# KeepUntil-v1_0.net
KiCad netlist of a schematic drawn in EAGLE
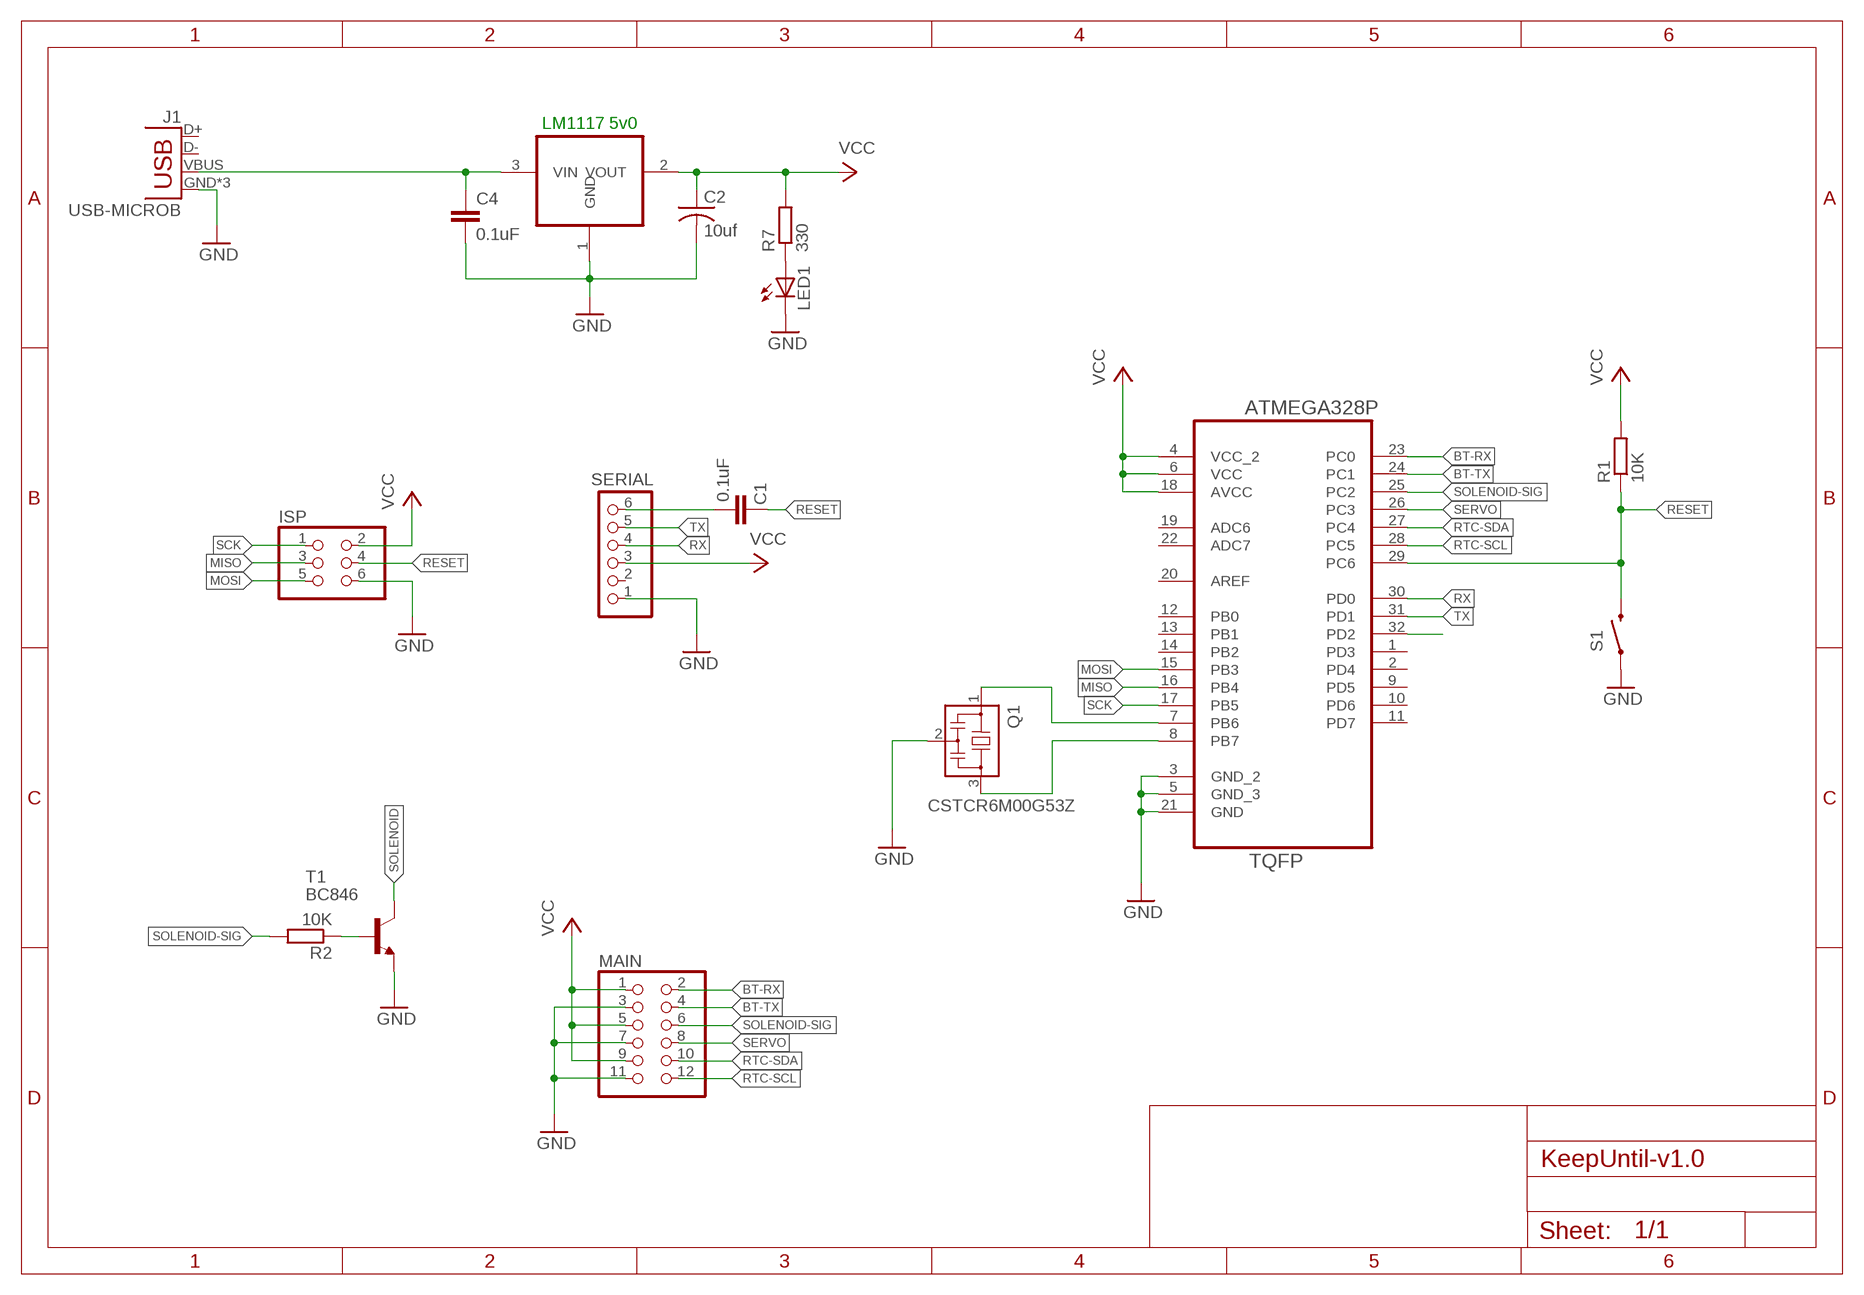
[diagram p0: schematic, sheet 1]

(export (version "E")
  (design (tool "Eeschema 10.0.6"))
  (components
    (comp (ref "C1")
      (value "0.1uF")
      (footprint "eagle-import:C0805")
      (libsource (lib "eagle-import") (part "C-EUC0805"))
    )
    (comp (ref "C2")
      (value "10uf")
      (footprint "eagle-import:C1206")
      (libsource (lib "eagle-import") (part "C-USC1206"))
    )
    (comp (ref "C4")
      (value "0.1uF")
      (footprint "eagle-import:C0805")
      (libsource (lib "eagle-import") (part "C-EUC0805"))
    )
    (comp (ref "IC2")
      (value "REG1117")
      (footprint "eagle-import:SOT223")
      (fields (field (name "MPN") "LM1117 3v3"))
      (libsource (lib "eagle-import") (part "REG1117"))
    )
    (comp (ref "ISP")
      (value "PINHD-2X3")
      (footprint "eagle-import:2X03")
      (libsource (lib "eagle-import") (part "PINHD-2X3"))
    )
    (comp (ref "J1")
      (value "USB-MICROB")
      (footprint "eagle-import:USB-MICROB")
      (libsource (lib "eagle-import") (part "USB-MICROB"))
    )
    (comp (ref "LED1")
      (value "LEDSMT1206")
      (footprint "eagle-import:1206")
      (libsource (lib "eagle-import") (part "LEDSMT1206"))
    )
    (comp (ref "MAIN")
      (value "PINHD-2X6")
      (footprint "eagle-import:2X06")
      (libsource (lib "eagle-import") (part "PINHD-2X6"))
    )
    (comp (ref "Q1")
      (value "CSTCR6M00G53Z")
      (footprint "eagle-import:CSTCR6M")
      (fields (field (name "MPN") "CSTCR6M00G53-R0"))
      (libsource (lib "eagle-import") (part "CSTCR6M00G53Z"))
    )
    (comp (ref "R1")
      (value "10K")
      (footprint "eagle-import:R0805")
      (libsource (lib "eagle-import") (part "R-EU_R0805"))
    )
    (comp (ref "R2")
      (value "10K")
      (footprint "eagle-import:R0805")
      (libsource (lib "eagle-import") (part "R-EU_R0805"))
    )
    (comp (ref "R7")
      (value "330")
      (footprint "eagle-import:R0805")
      (libsource (lib "eagle-import") (part "R-EU_R0805"))
    )
    (comp (ref "S1")
      (value "SWITCH-MOMENTARY-2SMD-1101NE")
      (footprint "eagle-import:TACTILE-SWITCH-1101NE")
      (libsource (lib "eagle-import") (part "SWITCH-MOMENTARY-2SMD-1101NE"))
    )
    (comp (ref "SERIAL")
      (value "PINHD-1X6")
      (footprint "eagle-import:1X06")
      (libsource (lib "eagle-import") (part "PINHD-1X6"))
    )
    (comp (ref "T1")
      (value "BC846")
      (footprint "eagle-import:SOT23")
      (libsource (lib "eagle-import") (part "BC846"))
    )
    (comp (ref "U1")
      (value "ATMEGA328P-AU")
      (footprint "eagle-import:QFP80P900X900X120-32N")
      (libsource (lib "eagle-import") (part "ATMEGA328P-AU"))
    )
  )
  (nets
    (net (code "1") (name "BT-RX") (class "Default")
      (node (ref "MAIN") (pin "2") (pinfunction "2_2") (pintype "passive"))
      (node (ref "U1") (pin "23") (pinfunction "PC0_23") (pintype "bidirectional"))
    )
    (net (code "2") (name "BT-TX") (class "Default")
      (node (ref "MAIN") (pin "4") (pinfunction "4_4") (pintype "passive"))
      (node (ref "U1") (pin "24") (pinfunction "PC1_24") (pintype "bidirectional"))
    )
    (net (code "3") (name "GND") (class "Default")
      (node (ref "C2") (pin "2") (pinfunction "2_2") (pintype "passive"))
      (node (ref "C4") (pin "2") (pinfunction "2_2") (pintype "passive"))
      (node (ref "IC2") (pin "1") (pinfunction "GND_1") (pintype "power_in"))
      (node (ref "ISP") (pin "6") (pinfunction "6_6") (pintype "passive"))
      (node (ref "J1") (pin "GND") (pinfunction "GND_GND") (pintype "bidirectional"))
      (node (ref "J1") (pin "MT1") (pinfunction "GND_MT1") (pintype "bidirectional"))
      (node (ref "J1") (pin "MT2") (pinfunction "GND_MT2") (pintype "bidirectional"))
      (node (ref "LED1") (pin "C") (pinfunction "C_C") (pintype "passive"))
      (node (ref "MAIN") (pin "11") (pinfunction "11_11") (pintype "passive"))
      (node (ref "MAIN") (pin "3") (pinfunction "3_3") (pintype "passive"))
      (node (ref "MAIN") (pin "7") (pinfunction "7_7") (pintype "passive"))
      (node (ref "Q1") (pin "2") (pinfunction "2_2") (pintype "passive"))
      (node (ref "S1") (pin "1") (pinfunction "1_1") (pintype "passive"))
      (node (ref "SERIAL") (pin "1") (pinfunction "1_1") (pintype "passive"))
      (node (ref "T1") (pin "2") (pinfunction "E_2") (pintype "passive"))
      (node (ref "U1") (pin "21") (pinfunction "GND_21") (pintype "passive"))
      (node (ref "U1") (pin "3") (pinfunction "GND_2_3") (pintype "passive"))
      (node (ref "U1") (pin "5") (pinfunction "GND_3_5") (pintype "passive"))
    )
    (net (code "4") (name "MISO") (class "Default")
      (node (ref "ISP") (pin "3") (pinfunction "3_3") (pintype "passive"))
      (node (ref "U1") (pin "16") (pinfunction "PB4_16") (pintype "bidirectional"))
    )
    (net (code "5") (name "MOSI") (class "Default")
      (node (ref "ISP") (pin "5") (pinfunction "5_5") (pintype "passive"))
      (node (ref "U1") (pin "15") (pinfunction "PB3_15") (pintype "bidirectional"))
    )
    (net (code "6") (name "Net-(C1-Pad2)") (class "Default")
      (node (ref "C1") (pin "2") (pinfunction "2_2") (pintype "passive"))
      (node (ref "SERIAL") (pin "6") (pinfunction "6_6") (pintype "passive"))
    )
    (net (code "7") (name "Net-(IC2-VIN)") (class "Default")
      (node (ref "C4") (pin "1") (pinfunction "1_1") (pintype "passive"))
      (node (ref "IC2") (pin "3") (pinfunction "VIN_3") (pintype "input"))
      (node (ref "J1") (pin "VBUS") (pinfunction "VBUS_VBUS") (pintype "bidirectional"))
    )
    (net (code "8") (name "Net-(LED1-PadA)") (class "Default")
      (node (ref "LED1") (pin "A") (pinfunction "A_A") (pintype "passive"))
      (node (ref "R7") (pin "1") (pinfunction "1_1") (pintype "passive"))
    )
    (net (code "9") (name "Net-(T1-B)") (class "Default")
      (node (ref "R2") (pin "1") (pinfunction "1_1") (pintype "passive"))
      (node (ref "T1") (pin "1") (pinfunction "B_1") (pintype "passive"))
    )
    (net (code "10") (name "Net-(U1-PB6)") (class "Default")
      (node (ref "Q1") (pin "1") (pinfunction "1_1") (pintype "passive"))
      (node (ref "U1") (pin "7") (pinfunction "PB6_7") (pintype "bidirectional"))
    )
    (net (code "11") (name "Net-(U1-PB7)") (class "Default")
      (node (ref "Q1") (pin "3") (pinfunction "3_3") (pintype "passive"))
      (node (ref "U1") (pin "8") (pinfunction "PB7_8") (pintype "bidirectional"))
    )
    (net (code "12") (name "RESET") (class "Default")
      (node (ref "C1") (pin "1") (pinfunction "1_1") (pintype "passive"))
      (node (ref "ISP") (pin "4") (pinfunction "4_4") (pintype "passive"))
      (node (ref "R1") (pin "1") (pinfunction "1_1") (pintype "passive"))
      (node (ref "S1") (pin "2") (pinfunction "2_2") (pintype "passive"))
      (node (ref "U1") (pin "29") (pinfunction "PC6_29") (pintype "bidirectional"))
    )
    (net (code "13") (name "RTC-SCL") (class "Default")
      (node (ref "MAIN") (pin "12") (pinfunction "12_12") (pintype "passive"))
      (node (ref "U1") (pin "28") (pinfunction "PC5_28") (pintype "bidirectional"))
    )
    (net (code "14") (name "RTC-SDA") (class "Default")
      (node (ref "MAIN") (pin "10") (pinfunction "10_10") (pintype "passive"))
      (node (ref "U1") (pin "27") (pinfunction "PC4_27") (pintype "bidirectional"))
    )
    (net (code "15") (name "RX") (class "Default")
      (node (ref "SERIAL") (pin "4") (pinfunction "4_4") (pintype "passive"))
      (node (ref "U1") (pin "30") (pinfunction "PD0_30") (pintype "bidirectional"))
    )
    (net (code "16") (name "SCK") (class "Default")
      (node (ref "ISP") (pin "1") (pinfunction "1_1") (pintype "passive"))
      (node (ref "U1") (pin "17") (pinfunction "PB5_17") (pintype "bidirectional"))
    )
    (net (code "17") (name "SERVO") (class "Default")
      (node (ref "MAIN") (pin "8") (pinfunction "8_8") (pintype "passive"))
      (node (ref "U1") (pin "26") (pinfunction "PC3_26") (pintype "bidirectional"))
    )
    (net (code "18") (name "SOLENOID") (class "Default")
      (node (ref "T1") (pin "3") (pinfunction "C_3") (pintype "passive"))
    )
    (net (code "19") (name "SOLENOID-SIG") (class "Default")
      (node (ref "MAIN") (pin "6") (pinfunction "6_6") (pintype "passive"))
      (node (ref "R2") (pin "2") (pinfunction "2_2") (pintype "passive"))
      (node (ref "U1") (pin "25") (pinfunction "PC2_25") (pintype "bidirectional"))
      (node (ref "U1") (pin "32") (pinfunction "PD2_32") (pintype "bidirectional"))
    )
    (net (code "20") (name "TX") (class "Default")
      (node (ref "SERIAL") (pin "5") (pinfunction "5_5") (pintype "passive"))
      (node (ref "U1") (pin "31") (pinfunction "PD1_31") (pintype "bidirectional"))
    )
    (net (code "21") (name "VCC") (class "Default")
      (node (ref "C2") (pin "1") (pinfunction "1_1") (pintype "passive"))
      (node (ref "IC2") (pin "2") (pinfunction "VOUT_2") (pintype "output"))
      (node (ref "ISP") (pin "2") (pinfunction "2_2") (pintype "passive"))
      (node (ref "MAIN") (pin "1") (pinfunction "1_1") (pintype "passive"))
      (node (ref "MAIN") (pin "5") (pinfunction "5_5") (pintype "passive"))
      (node (ref "MAIN") (pin "9") (pinfunction "9_9") (pintype "passive"))
      (node (ref "R1") (pin "2") (pinfunction "2_2") (pintype "passive"))
      (node (ref "R7") (pin "2") (pinfunction "2_2") (pintype "passive"))
      (node (ref "SERIAL") (pin "3") (pinfunction "3_3") (pintype "passive"))
      (node (ref "U1") (pin "18") (pinfunction "AVCC_18") (pintype "power_in"))
      (node (ref "U1") (pin "4") (pinfunction "VCC_2_4") (pintype "power_in"))
      (node (ref "U1") (pin "6") (pinfunction "VCC_6") (pintype "power_in"))
    )
    (net (code "22") (name "unconnected-(J1-PadD+)") (class "Default")
      (node (ref "J1") (pin "D+") (pinfunction "D+_D+") (pintype "bidirectional"))
    )
    (net (code "23") (name "unconnected-(J1-PadD-)") (class "Default")
      (node (ref "J1") (pin "D-") (pinfunction "D-_D-") (pintype "bidirectional"))
    )
    (net (code "24") (name "unconnected-(SERIAL-Pad2)") (class "Default")
      (node (ref "SERIAL") (pin "2") (pinfunction "2_2") (pintype "passive"))
    )
    (net (code "25") (name "unconnected-(U1-ADC6-Pad19)") (class "Default")
      (node (ref "U1") (pin "19") (pinfunction "ADC6_19") (pintype "input"))
    )
    (net (code "26") (name "unconnected-(U1-ADC7-Pad22)") (class "Default")
      (node (ref "U1") (pin "22") (pinfunction "ADC7_22") (pintype "input"))
    )
    (net (code "27") (name "unconnected-(U1-AREF-Pad20)") (class "Default")
      (node (ref "U1") (pin "20") (pinfunction "AREF_20") (pintype "input"))
    )
    (net (code "28") (name "unconnected-(U1-PB0-Pad12)") (class "Default")
      (node (ref "U1") (pin "12") (pinfunction "PB0_12") (pintype "bidirectional"))
    )
    (net (code "29") (name "unconnected-(U1-PB1-Pad13)") (class "Default")
      (node (ref "U1") (pin "13") (pinfunction "PB1_13") (pintype "bidirectional"))
    )
    (net (code "30") (name "unconnected-(U1-PB2-Pad14)") (class "Default")
      (node (ref "U1") (pin "14") (pinfunction "PB2_14") (pintype "bidirectional"))
    )
    (net (code "31") (name "unconnected-(U1-PD3-Pad1)") (class "Default")
      (node (ref "U1") (pin "1") (pinfunction "PD3_1") (pintype "bidirectional"))
    )
    (net (code "32") (name "unconnected-(U1-PD4-Pad2)") (class "Default")
      (node (ref "U1") (pin "2") (pinfunction "PD4_2") (pintype "bidirectional"))
    )
    (net (code "33") (name "unconnected-(U1-PD5-Pad9)") (class "Default")
      (node (ref "U1") (pin "9") (pinfunction "PD5_9") (pintype "bidirectional"))
    )
    (net (code "34") (name "unconnected-(U1-PD6-Pad10)") (class "Default")
      (node (ref "U1") (pin "10") (pinfunction "PD6_10") (pintype "bidirectional"))
    )
    (net (code "35") (name "unconnected-(U1-PD7-Pad11)") (class "Default")
      (node (ref "U1") (pin "11") (pinfunction "PD7_11") (pintype "bidirectional"))
    )
  )
)
